# valve_driver.net
KiCad netlist of a schematic drawn in Altium Designer
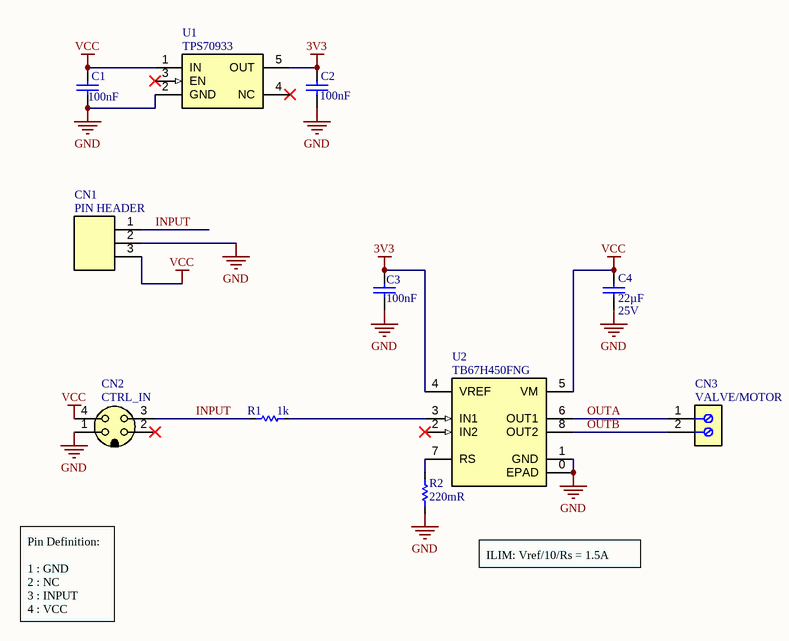
[diagram p0: valve driver.SchDoc]

(export (version "E")
  (design (tool "Eeschema 10.0.6"))
  (components
    (comp (ref "C1")
      (value "100nF")
      (footprint "CAP_CHIP_0603")
      (description "0603 Multilayer Ceramic Capacitors MLCC")
      (fields (field (name "TOLERANCE") "10%") (field (name "PARTNUMBER") "CC0603KRX7R9BB104"))
      (libsource (lib "Sainsbury Wellcome Centre") (part "Cap"))
    )
    (comp (ref "C2")
      (value "100nF")
      (footprint "CAP_CHIP_0603")
      (description "0603 Multilayer Ceramic Capacitors MLCC")
      (fields (field (name "TOLERANCE") "10%") (field (name "PARTNUMBER") "CC0603KRX7R9BB104"))
      (libsource (lib "Sainsbury Wellcome Centre") (part "Cap"))
    )
    (comp (ref "C3")
      (value "100nF")
      (footprint "CAP_CHIP_0603")
      (description "0603 Multilayer Ceramic Capacitors MLCC")
      (fields (field (name "TOLERANCE") "10%") (field (name "PARTNUMBER") "CC0603KRX7R9BB104"))
      (libsource (lib "Sainsbury Wellcome Centre") (part "Cap"))
    )
    (comp (ref "C4")
      (value "22µF")
      (footprint "CAP_CHIP_0805")
      (description "0805 Multilayer Ceramic Capacitors MLCC")
      (fields
        (field (name "VOLTAGE RATING") "25V")
        (field (name "TOLERANCE") "20%")
        (field (name "PARTNUMBER") "CL21A226MAQNNNE")
      )
      (libsource (lib "Sainsbury Wellcome Centre") (part "Cap"))
    )
    (comp (ref "CN1")
      (value "PIN HEADER")
      (footprint "PIN_2.54_90_1X3P")
      (description "Through Hole,Right Angle,P=2.54mm")
      (fields (field (name "PARTNUMBER") "PZ254R-11-03P"))
      (libsource (lib "Sainsbury Wellcome Centre") (part "Header_1X3P"))
    )
    (comp (ref "CN2")
      (value "CTRL_IN")
      (footprint "853-004-213R00Y")
      (description "CONN PLUG FMALE 4POS GOLD SOLDER")
      (fields (field (name "PARTNUMBER") "853-004-213R001"))
      (libsource (lib "Sainsbury Wellcome Centre") (part "Circular_4P"))
    )
    (comp (ref "CN3")
      (value "VALVE/MOTOR")
      (footprint "TH-5.00-1X2P")
      (description "1x2P 20A -40℃~+105℃ 250V Green 12~22 Direct Insert 5mm 2.5 1 2 Plugin,P=5mm Screw Terminal Blocks")
      (fields (field (name "PARTNUMBER") "WJ128V-5.0-2P"))
      (libsource (lib "Sainsbury Wellcome Centre") (part "Terminal Block 2"))
    )
    (comp (ref "R1")
      (value "1k")
      (footprint "RES_CHIP_0603")
      (description "100mW Thick Film Resistors 75V ±100ppm/℃ ±1% 0603 Chip Resistor")
      (fields (field (name "PARTNUMBER") "0603WAF1001T5E") (field (name "TOLERANCE") "1%"))
      (libsource (lib "Sainsbury Wellcome Centre") (part "Res"))
    )
    (comp (ref "R2")
      (value "220mR")
      (footprint "RES_CHIP_0805")
      (description "Res Thick Film 0805 0.22 Ohm 1% 0.5W(1/2W) 0ppm/C to 100ppm/C Pad SMD T/R Automotive AEC-Q200")
      (fields (field (name "TOLERANCE") "1%") (field (name "PARTNUMBER") "ERJ-6DQFR22V"))
      (libsource (lib "Sainsbury Wellcome Centre") (part "Res"))
    )
    (comp (ref "U1")
      (value "TPS70933")
      (footprint "SOT23-5")
      (description "LDO Regulator Pos 3.3V 0.15A 5-Pin SOT-23 T/R")
      (fields (field (name "PARTNUMBER") "TPS70933DBVR"))
      (libsource (lib "Sainsbury Wellcome Centre") (part "LDO-5P-NC"))
    )
    (comp (ref "U2")
      (value "TB67H450FNG")
      (footprint "SOIC8_EP_TI")
      (description "Brushed Motor Driver IC, 50V, 3.5A, SOP8 Package")
      (libsource (lib "Sainsbury Wellcome Centre") (part "TB67H450FNG"))
    )
  )
  (nets
    (net (code "1") (name "/INPUT") (class "Default")
      (node (ref "CN1") (pin "1") (pinfunction "1_1") (pintype "passive"))
      (node (ref "CN2") (pin "3") (pinfunction "3_3") (pintype "passive"))
      (node (ref "R1") (pin "1") (pinfunction "1_1") (pintype "passive"))
    )
    (net (code "2") (name "/OUTA") (class "Default")
      (node (ref "CN3") (pin "1") (pinfunction "1_1") (pintype "passive"))
      (node (ref "U2") (pin "6") (pinfunction "OUT1_6") (pintype "passive"))
    )
    (net (code "3") (name "/OUTB") (class "Default")
      (node (ref "CN3") (pin "2") (pinfunction "2_2") (pintype "passive"))
      (node (ref "U2") (pin "8") (pinfunction "OUT2_8") (pintype "passive"))
    )
    (net (code "4") (name "3V3") (class "Default")
      (node (ref "C2") (pin "2") (pinfunction "2_2") (pintype "passive"))
      (node (ref "C3") (pin "2") (pinfunction "2_2") (pintype "passive"))
      (node (ref "U1") (pin "5") (pinfunction "OUT_5") (pintype "power_in"))
      (node (ref "U2") (pin "4") (pinfunction "VREF_4") (pintype "power_in"))
    )
    (net (code "5") (name "GND") (class "Default")
      (node (ref "C1") (pin "1") (pinfunction "1_1") (pintype "passive"))
      (node (ref "C2") (pin "1") (pinfunction "1_1") (pintype "passive"))
      (node (ref "C3") (pin "1") (pinfunction "1_1") (pintype "passive"))
      (node (ref "C4") (pin "1") (pinfunction "1_1") (pintype "passive"))
      (node (ref "CN1") (pin "2") (pinfunction "2_2") (pintype "passive"))
      (node (ref "CN2") (pin "1") (pinfunction "1_1") (pintype "passive"))
      (node (ref "R2") (pin "1") (pinfunction "1_1") (pintype "passive"))
      (node (ref "U1") (pin "2") (pinfunction "GND_2") (pintype "power_in"))
      (node (ref "U2") (pin "0") (pinfunction "EPAD_0") (pintype "power_in"))
      (node (ref "U2") (pin "1") (pinfunction "GND_1") (pintype "power_in"))
    )
    (net (code "6") (name "Net-(U2-IN1)") (class "Default")
      (node (ref "R1") (pin "2") (pinfunction "2_2") (pintype "passive"))
      (node (ref "U2") (pin "3") (pinfunction "IN1_3") (pintype "input"))
    )
    (net (code "7") (name "Net-(U2-RS)") (class "Default")
      (node (ref "R2") (pin "2") (pinfunction "2_2") (pintype "passive"))
      (node (ref "U2") (pin "7") (pinfunction "RS_7") (pintype "passive"))
    )
    (net (code "8") (name "VCC") (class "Default")
      (node (ref "C1") (pin "2") (pinfunction "2_2") (pintype "passive"))
      (node (ref "C4") (pin "2") (pinfunction "2_2") (pintype "passive"))
      (node (ref "CN1") (pin "3") (pinfunction "3_3") (pintype "passive"))
      (node (ref "CN2") (pin "4") (pinfunction "4_4") (pintype "passive"))
      (node (ref "U1") (pin "1") (pinfunction "IN_1") (pintype "power_in"))
      (node (ref "U2") (pin "5") (pinfunction "VM_5") (pintype "power_in"))
    )
    (net (code "9") (name "unconnected-(CN2-Pad2)") (class "Default")
      (node (ref "CN2") (pin "2") (pinfunction "2_2") (pintype "passive+no_connect"))
    )
    (net (code "10") (name "unconnected-(U1-EN-Pad3)") (class "Default")
      (node (ref "U1") (pin "3") (pinfunction "EN_3") (pintype "input+no_connect"))
    )
    (net (code "11") (name "unconnected-(U1-NC-Pad4)") (class "Default")
      (node (ref "U1") (pin "4") (pinfunction "NC_4") (pintype "passive+no_connect"))
    )
    (net (code "12") (name "unconnected-(U2-IN2-Pad2)") (class "Default")
      (node (ref "U2") (pin "2") (pinfunction "IN2_2") (pintype "input+no_connect"))
    )
  )
)
